# SOIC_TSSOP-20_600mil_DIP.net
KiCad netlist of a schematic drawn in EAGLE
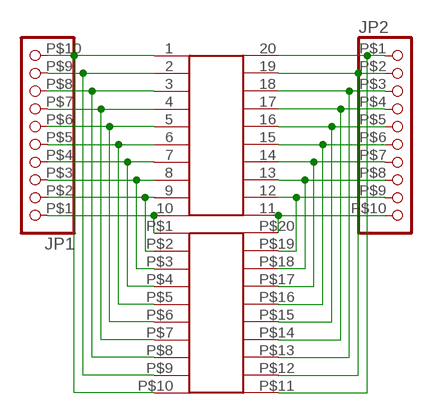
[diagram p0: schematic, sheet 1]

(export (version "E")
  (design (tool "Eeschema 10.0.6"))
  (components
    (comp (ref "JP1")
      (value "PINHD-1X10THIN")
      (footprint "eagle-import:HEADER1X10")
      (libsource (lib "eagle-import") (part "PINHD-1X10THIN"))
    )
    (comp (ref "JP2")
      (value "PINHD-1X10THIN")
      (footprint "eagle-import:HEADER1X10")
      (libsource (lib "eagle-import") (part "PINHD-1X10THIN"))
    )
    (comp (ref "U$1")
      (value "SMD-20TSSOP")
      (footprint "eagle-import:TSSOP-20NM")
      (libsource (lib "eagle-import") (part "SMD-20TSSOP"))
    )
    (comp (ref "U$2")
      (value "SMD-20SOIC")
      (footprint "eagle-import:SO-20NMW")
      (libsource (lib "eagle-import") (part "SMD-20SOIC"))
    )
  )
  (nets
    (net (code "1") (name "Net-(JP1-1)") (class "Default")
      (node (ref "JP1") (pin "P$1") (pinfunction "1_P$1") (pintype "passive"))
      (node (ref "U$1") (pin "10") (pinfunction "P$10_10") (pintype "bidirectional"))
      (node (ref "U$2") (pin "P$1") (pinfunction "P$1_P$1") (pintype "bidirectional"))
    )
    (net (code "2") (name "Net-(JP1-2)") (class "Default")
      (node (ref "JP1") (pin "P$2") (pinfunction "2_P$2") (pintype "passive"))
      (node (ref "U$1") (pin "9") (pinfunction "P$9_9") (pintype "bidirectional"))
      (node (ref "U$2") (pin "P$2") (pinfunction "P$2_P$2") (pintype "bidirectional"))
    )
    (net (code "3") (name "Net-(JP1-3)") (class "Default")
      (node (ref "JP1") (pin "P$3") (pinfunction "3_P$3") (pintype "passive"))
      (node (ref "U$1") (pin "8") (pinfunction "P$8_8") (pintype "bidirectional"))
      (node (ref "U$2") (pin "P$3") (pinfunction "P$3_P$3") (pintype "bidirectional"))
    )
    (net (code "4") (name "Net-(JP1-4)") (class "Default")
      (node (ref "JP1") (pin "P$4") (pinfunction "4_P$4") (pintype "passive"))
      (node (ref "U$1") (pin "7") (pinfunction "P$7_7") (pintype "bidirectional"))
      (node (ref "U$2") (pin "P$4") (pinfunction "P$4_P$4") (pintype "bidirectional"))
    )
    (net (code "5") (name "Net-(JP1-5)") (class "Default")
      (node (ref "JP1") (pin "P$5") (pinfunction "5_P$5") (pintype "passive"))
      (node (ref "U$1") (pin "6") (pinfunction "P$6_6") (pintype "bidirectional"))
      (node (ref "U$2") (pin "P$5") (pinfunction "P$5_P$5") (pintype "bidirectional"))
    )
    (net (code "6") (name "Net-(JP1-6)") (class "Default")
      (node (ref "JP1") (pin "P$6") (pinfunction "6_P$6") (pintype "passive"))
      (node (ref "U$1") (pin "5") (pinfunction "P$5_5") (pintype "bidirectional"))
      (node (ref "U$2") (pin "P$6") (pinfunction "P$6_P$6") (pintype "bidirectional"))
    )
    (net (code "7") (name "Net-(JP1-7)") (class "Default")
      (node (ref "JP1") (pin "P$7") (pinfunction "7_P$7") (pintype "passive"))
      (node (ref "U$1") (pin "4") (pinfunction "P$4_4") (pintype "bidirectional"))
      (node (ref "U$2") (pin "P$7") (pinfunction "P$7_P$7") (pintype "bidirectional"))
    )
    (net (code "8") (name "Net-(JP1-8)") (class "Default")
      (node (ref "JP1") (pin "P$8") (pinfunction "8_P$8") (pintype "passive"))
      (node (ref "U$1") (pin "3") (pinfunction "P$3_3") (pintype "bidirectional"))
      (node (ref "U$2") (pin "P$8") (pinfunction "P$8_P$8") (pintype "bidirectional"))
    )
    (net (code "9") (name "Net-(JP1-9)") (class "Default")
      (node (ref "JP1") (pin "P$9") (pinfunction "9_P$9") (pintype "passive"))
      (node (ref "U$1") (pin "2") (pinfunction "P$2_2") (pintype "bidirectional"))
      (node (ref "U$2") (pin "P$9") (pinfunction "P$9_P$9") (pintype "bidirectional"))
    )
    (net (code "10") (name "Net-(JP1-10)") (class "Default")
      (node (ref "JP1") (pin "P$10") (pinfunction "10_P$10") (pintype "passive"))
      (node (ref "U$1") (pin "1") (pinfunction "P$1_1") (pintype "bidirectional"))
      (node (ref "U$2") (pin "P$10") (pinfunction "P$10_P$10") (pintype "bidirectional"))
    )
    (net (code "11") (name "Net-(JP2-1)") (class "Default")
      (node (ref "JP2") (pin "P$1") (pinfunction "1_P$1") (pintype "passive"))
      (node (ref "U$1") (pin "20") (pinfunction "P$20_20") (pintype "bidirectional"))
      (node (ref "U$2") (pin "P$11") (pinfunction "P$11_P$11") (pintype "bidirectional"))
    )
    (net (code "12") (name "Net-(JP2-2)") (class "Default")
      (node (ref "JP2") (pin "P$2") (pinfunction "2_P$2") (pintype "passive"))
      (node (ref "U$1") (pin "19") (pinfunction "P$19_19") (pintype "bidirectional"))
      (node (ref "U$2") (pin "P$12") (pinfunction "P$12_P$12") (pintype "bidirectional"))
    )
    (net (code "13") (name "Net-(JP2-3)") (class "Default")
      (node (ref "JP2") (pin "P$3") (pinfunction "3_P$3") (pintype "passive"))
      (node (ref "U$1") (pin "18") (pinfunction "P$18_18") (pintype "bidirectional"))
      (node (ref "U$2") (pin "P$13") (pinfunction "P$13_P$13") (pintype "bidirectional"))
    )
    (net (code "14") (name "Net-(JP2-4)") (class "Default")
      (node (ref "JP2") (pin "P$4") (pinfunction "4_P$4") (pintype "passive"))
      (node (ref "U$1") (pin "17") (pinfunction "P$17_17") (pintype "bidirectional"))
      (node (ref "U$2") (pin "P$14") (pinfunction "P$14_P$14") (pintype "bidirectional"))
    )
    (net (code "15") (name "Net-(JP2-5)") (class "Default")
      (node (ref "JP2") (pin "P$5") (pinfunction "5_P$5") (pintype "passive"))
      (node (ref "U$1") (pin "16") (pinfunction "P$16_16") (pintype "bidirectional"))
      (node (ref "U$2") (pin "P$15") (pinfunction "P$15_P$15") (pintype "bidirectional"))
    )
    (net (code "16") (name "Net-(JP2-6)") (class "Default")
      (node (ref "JP2") (pin "P$6") (pinfunction "6_P$6") (pintype "passive"))
      (node (ref "U$1") (pin "15") (pinfunction "P$15_15") (pintype "bidirectional"))
      (node (ref "U$2") (pin "P$16") (pinfunction "P$16_P$16") (pintype "bidirectional"))
    )
    (net (code "17") (name "Net-(JP2-7)") (class "Default")
      (node (ref "JP2") (pin "P$7") (pinfunction "7_P$7") (pintype "passive"))
      (node (ref "U$1") (pin "14") (pinfunction "P$14_14") (pintype "bidirectional"))
      (node (ref "U$2") (pin "P$17") (pinfunction "P$17_P$17") (pintype "bidirectional"))
    )
    (net (code "18") (name "Net-(JP2-8)") (class "Default")
      (node (ref "JP2") (pin "P$8") (pinfunction "8_P$8") (pintype "passive"))
      (node (ref "U$1") (pin "13") (pinfunction "P$13_13") (pintype "bidirectional"))
      (node (ref "U$2") (pin "P$18") (pinfunction "P$18_P$18") (pintype "bidirectional"))
    )
    (net (code "19") (name "Net-(JP2-9)") (class "Default")
      (node (ref "JP2") (pin "P$9") (pinfunction "9_P$9") (pintype "passive"))
      (node (ref "U$1") (pin "12") (pinfunction "P$12_12") (pintype "bidirectional"))
      (node (ref "U$2") (pin "P$19") (pinfunction "P$19_P$19") (pintype "bidirectional"))
    )
    (net (code "20") (name "Net-(JP2-10)") (class "Default")
      (node (ref "JP2") (pin "P$10") (pinfunction "10_P$10") (pintype "passive"))
      (node (ref "U$1") (pin "11") (pinfunction "P$11_11") (pintype "bidirectional"))
      (node (ref "U$2") (pin "P$20") (pinfunction "P$20_P$20") (pintype "bidirectional"))
    )
  )
)
